# tracksoar_shield.net
KiCad netlist of a schematic drawn in EAGLE
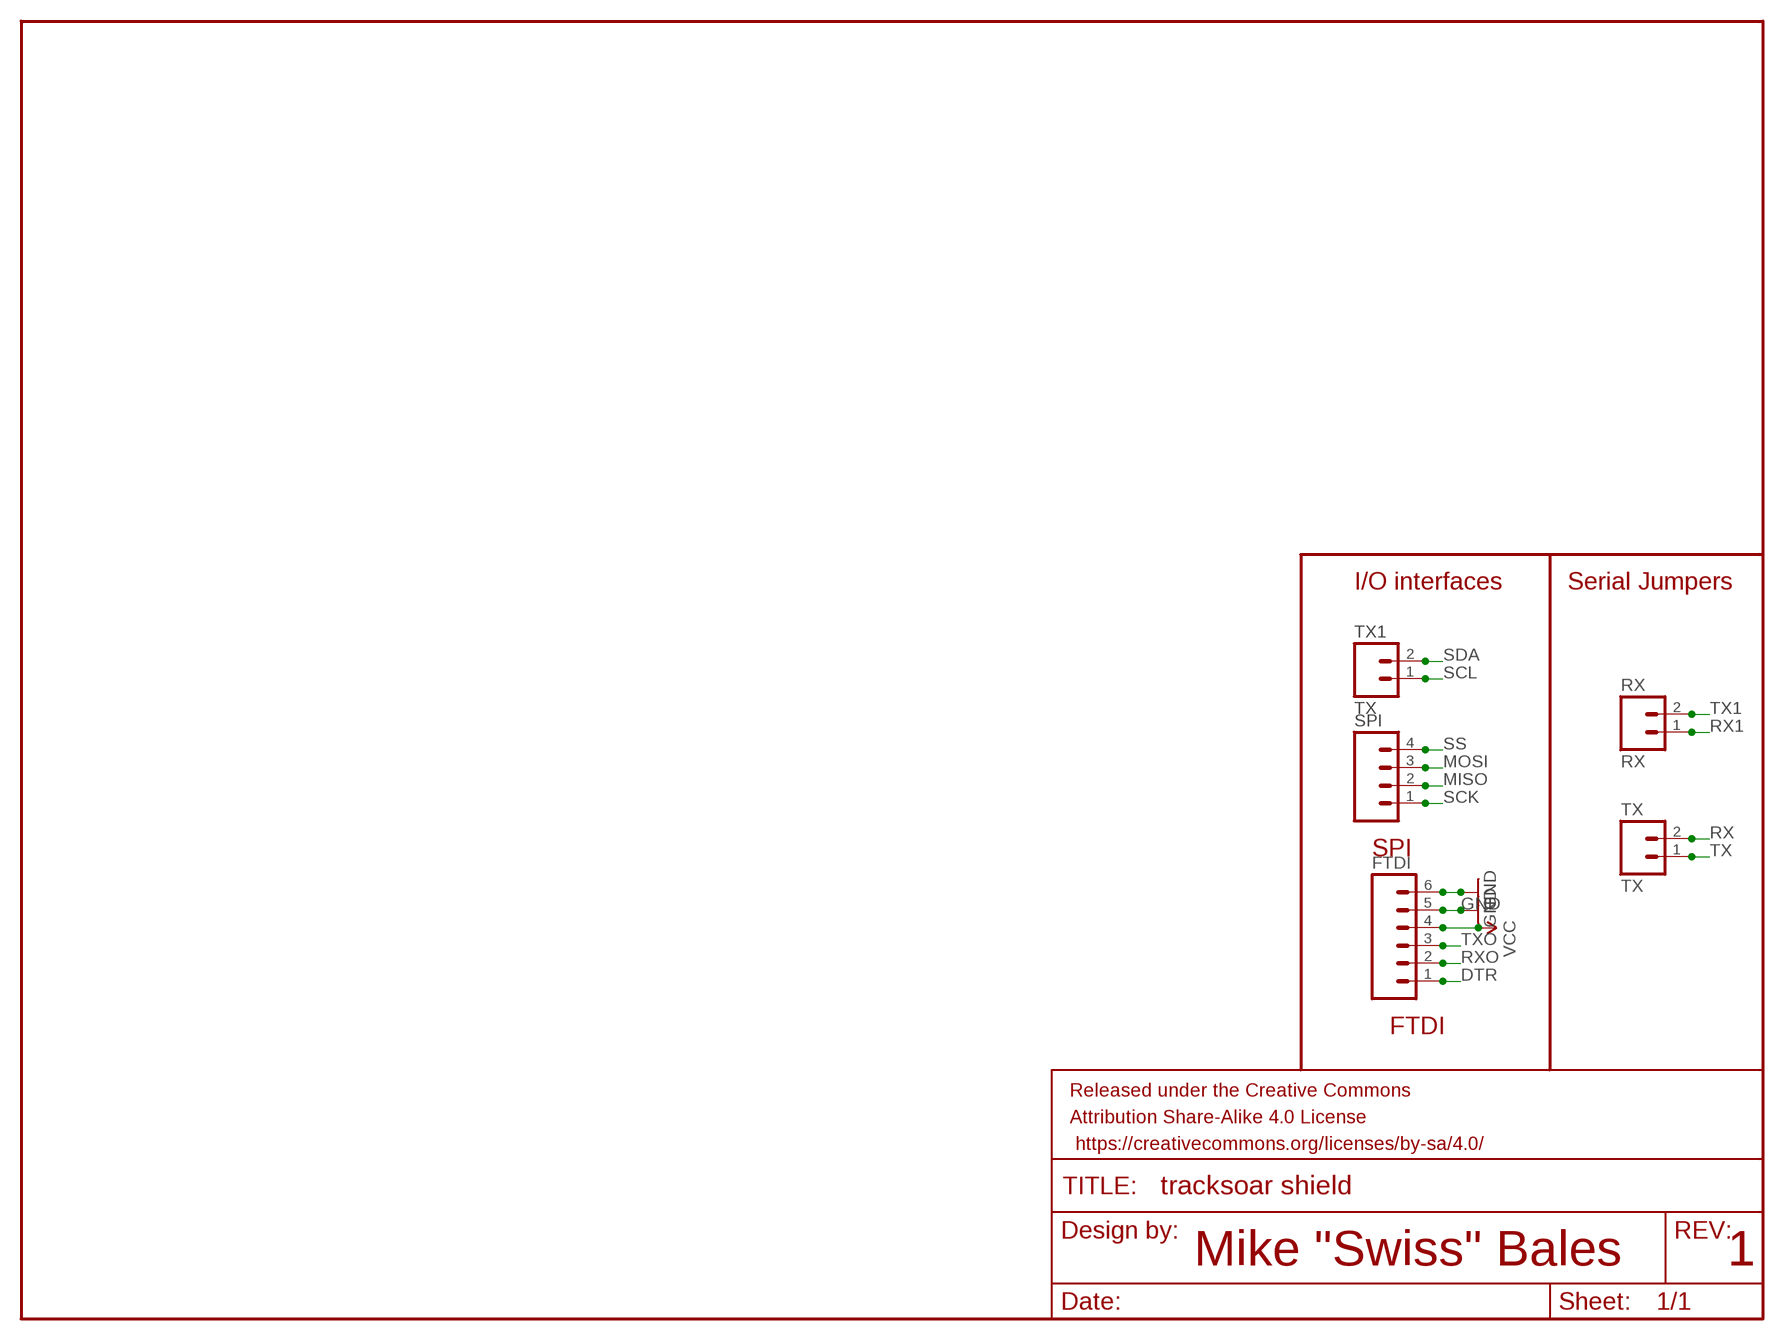
[diagram p0: schematic, sheet 1]

(export (version "E")
  (design (tool "Eeschema 10.0.6"))
  (components
    (comp (ref "FRAME1")
      (value "FRAME-LETTER")
      (footprint "eagle-import:CREATIVE_COMMONS")
      (libsource (lib "eagle-import") (part "FRAME-LETTER"))
    )
    (comp (ref "FTDI")
      (value "M06NO_SILK_FEMALE_PTH")
      (footprint "eagle-import:1X06_NO_SILK")
      (libsource (lib "eagle-import") (part "M06NO_SILK_FEMALE_PTH"))
    )
    (comp (ref "RX")
      (value "RX")
      (footprint "eagle-import:JST-2-PTH-VERT")
      (libsource (lib "eagle-import") (part "M02JST-PTH-VERT"))
    )
    (comp (ref "SPI")
      (value "M04JST-PTH-VERT")
      (footprint "eagle-import:JST-4-PTH-VERT")
      (libsource (lib "eagle-import") (part "M04JST-PTH-VERT"))
    )
    (comp (ref "TX")
      (value "TX")
      (footprint "eagle-import:JST-2-PTH-VERT")
      (libsource (lib "eagle-import") (part "M02JST-PTH-VERT"))
    )
    (comp (ref "TX1")
      (value "TX")
      (footprint "eagle-import:JST-2-PTH-VERT")
      (libsource (lib "eagle-import") (part "M02JST-PTH-VERT"))
    )
  )
  (nets
    (net (code "1") (name "/DTR") (class "Default")
      (node (ref "FTDI") (pin "1") (pinfunction "1_1") (pintype "passive"))
    )
    (net (code "2") (name "/MISO") (class "Default")
      (node (ref "SPI") (pin "2") (pinfunction "2_2") (pintype "passive"))
    )
    (net (code "3") (name "/MOSI") (class "Default")
      (node (ref "SPI") (pin "3") (pinfunction "3_3") (pintype "passive"))
    )
    (net (code "4") (name "/RX") (class "Default")
      (node (ref "TX") (pin "2") (pinfunction "2_2") (pintype "passive"))
    )
    (net (code "5") (name "/RX1") (class "Default")
      (node (ref "RX") (pin "1") (pinfunction "1_1") (pintype "passive"))
    )
    (net (code "6") (name "/RXO") (class "Default")
      (node (ref "FTDI") (pin "2") (pinfunction "2_2") (pintype "passive"))
    )
    (net (code "7") (name "/SCK") (class "Default")
      (node (ref "SPI") (pin "1") (pinfunction "1_1") (pintype "passive"))
    )
    (net (code "8") (name "/SCL") (class "Default")
      (node (ref "TX1") (pin "1") (pinfunction "1_1") (pintype "passive"))
    )
    (net (code "9") (name "/SDA") (class "Default")
      (node (ref "TX1") (pin "2") (pinfunction "2_2") (pintype "passive"))
    )
    (net (code "10") (name "/SS") (class "Default")
      (node (ref "SPI") (pin "4") (pinfunction "4_4") (pintype "passive"))
    )
    (net (code "11") (name "/TX") (class "Default")
      (node (ref "TX") (pin "1") (pinfunction "1_1") (pintype "passive"))
    )
    (net (code "12") (name "/TX1") (class "Default")
      (node (ref "RX") (pin "2") (pinfunction "2_2") (pintype "passive"))
    )
    (net (code "13") (name "/TXO") (class "Default")
      (node (ref "FTDI") (pin "3") (pinfunction "3_3") (pintype "passive"))
    )
    (net (code "14") (name "GND") (class "Default")
      (node (ref "FTDI") (pin "5") (pinfunction "5_5") (pintype "passive"))
      (node (ref "FTDI") (pin "6") (pinfunction "6_6") (pintype "passive"))
    )
    (net (code "15") (name "VCC") (class "Default")
      (node (ref "FTDI") (pin "4") (pinfunction "4_4") (pintype "passive"))
    )
  )
)
